# ArduinoShield.net
KiCad netlist of a schematic drawn in EAGLE
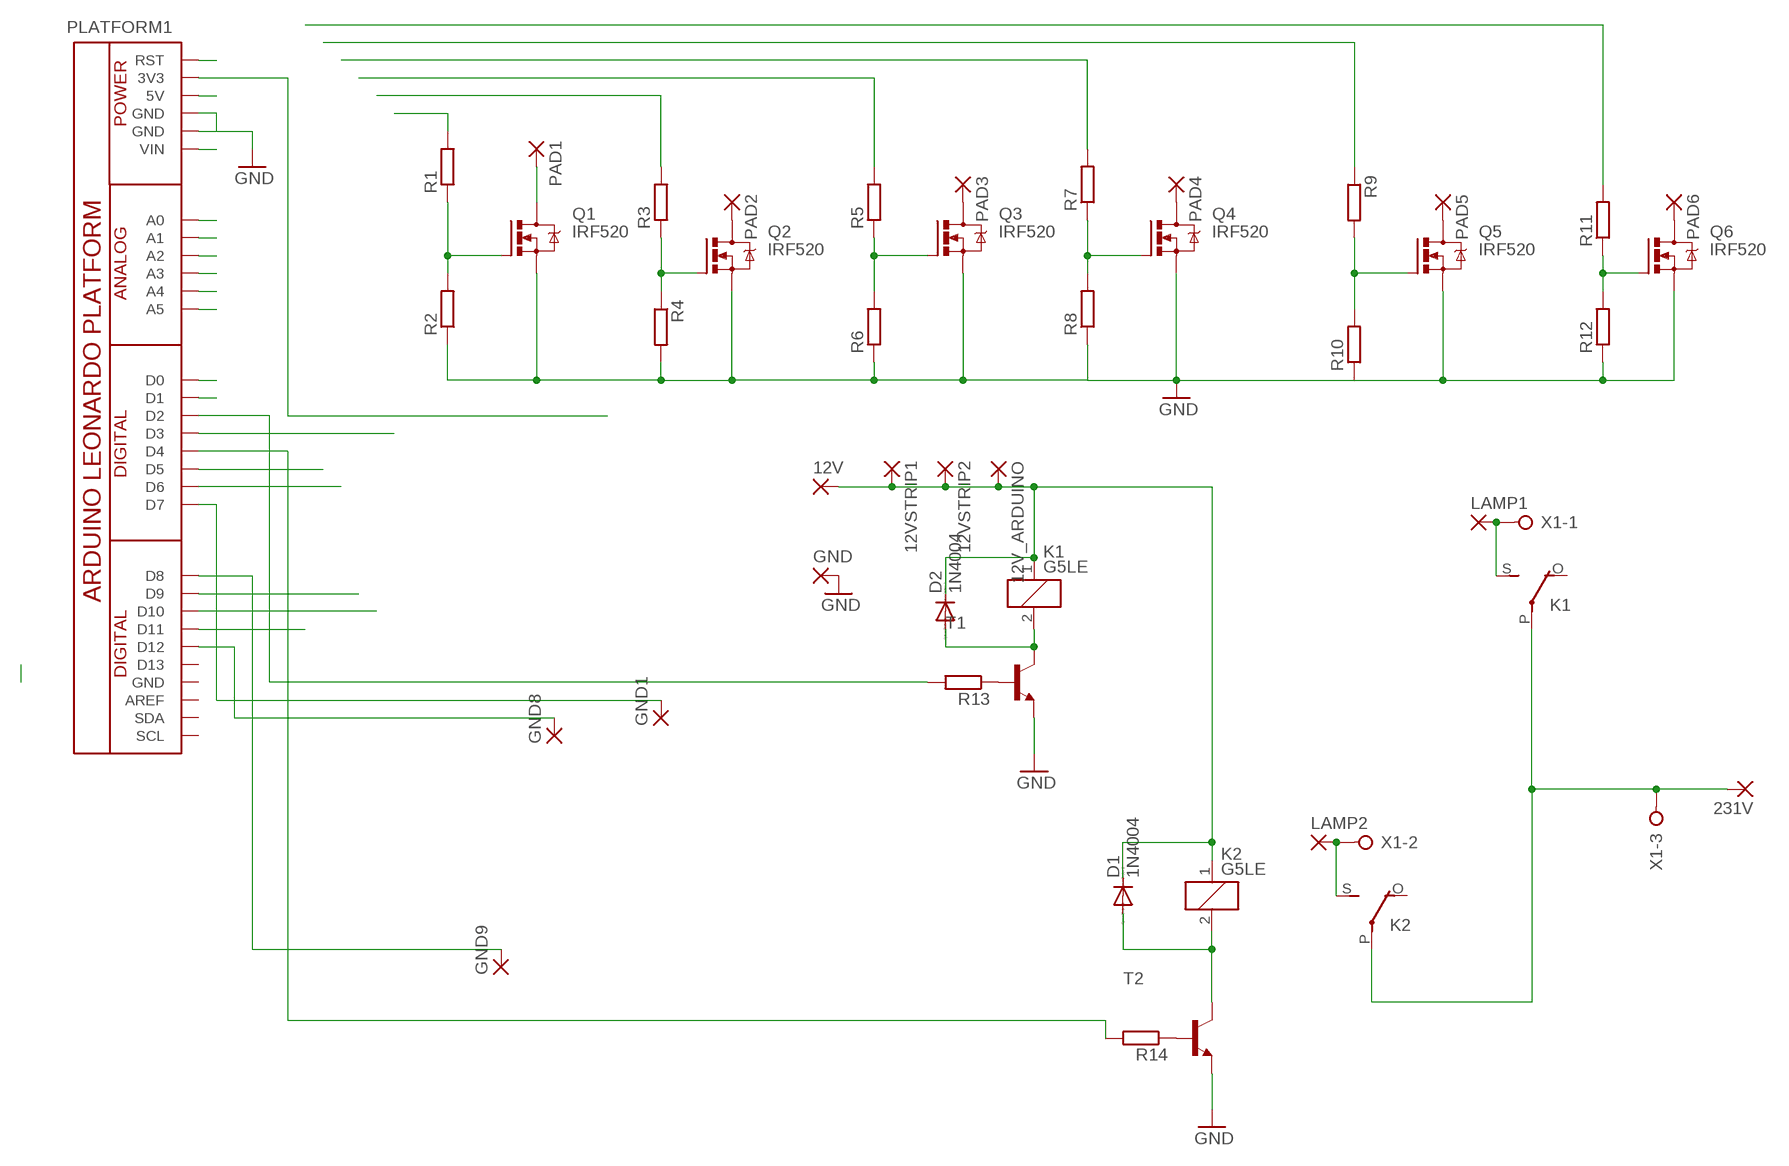
[diagram p0: schematic, sheet 1]

(export (version "E")
  (design (tool "Eeschema 10.0.6"))
  (components
    (comp (ref "12V")
      (value "WIREPAD1,6/0,8")
      (footprint "eagle-import:1,6_0,8")
      (libsource (lib "eagle-import") (part "WIREPAD1,6/0,8"))
    )
    (comp (ref "12VSTRIP1")
      (value "WIREPAD1,6/0,8")
      (footprint "eagle-import:1,6_0,8")
      (libsource (lib "eagle-import") (part "WIREPAD1,6/0,8"))
    )
    (comp (ref "12VSTRIP2")
      (value "WIREPAD1,6/0,8")
      (footprint "eagle-import:1,6_0,8")
      (libsource (lib "eagle-import") (part "WIREPAD1,6/0,8"))
    )
    (comp (ref "12V_ARDUINO")
      (value "WIREPAD1,6/0,8")
      (footprint "eagle-import:1,6_0,8")
      (libsource (lib "eagle-import") (part "WIREPAD1,6/0,8"))
    )
    (comp (ref "231V")
      (value "WIREPAD1,6/0,8")
      (footprint "eagle-import:1,6_0,8")
      (libsource (lib "eagle-import") (part "WIREPAD1,6/0,8"))
    )
    (comp (ref "D1")
      (value "1N4004")
      (footprint "eagle-import:DO41-10")
      (libsource (lib "eagle-import") (part "1N4004"))
    )
    (comp (ref "D2")
      (value "1N4004")
      (footprint "eagle-import:DO41-10")
      (libsource (lib "eagle-import") (part "1N4004"))
    )
    (comp (ref "GND")
      (value "WIREPAD1,6/0,8")
      (footprint "eagle-import:1,6_0,8")
      (libsource (lib "eagle-import") (part "WIREPAD1,6/0,8"))
    )
    (comp (ref "GND1")
      (value "WIREPAD1,6/0,8")
      (footprint "eagle-import:1,6_0,8")
      (libsource (lib "eagle-import") (part "WIREPAD1,6/0,8"))
    )
    (comp (ref "GND8")
      (value "WIREPAD1,6/0,8")
      (footprint "eagle-import:1,6_0,8")
      (libsource (lib "eagle-import") (part "WIREPAD1,6/0,8"))
    )
    (comp (ref "GND9")
      (value "WIREPAD1,6/0,8")
      (footprint "eagle-import:1,6_0,8")
      (libsource (lib "eagle-import") (part "WIREPAD1,6/0,8"))
    )
    (comp (ref "K1")
      (value "G5LE")
      (footprint "eagle-import:G5LE")
      (libsource (lib "eagle-import") (part "G5LE"))
    )
    (comp (ref "K2")
      (value "G5LE")
      (footprint "eagle-import:G5LE")
      (libsource (lib "eagle-import") (part "G5LE"))
    )
    (comp (ref "LAMP1")
      (value "WIREPAD1,6/0,8")
      (footprint "eagle-import:1,6_0,8")
      (libsource (lib "eagle-import") (part "WIREPAD1,6/0,8"))
    )
    (comp (ref "LAMP2")
      (value "WIREPAD1,6/0,8")
      (footprint "eagle-import:1,6_0,8")
      (libsource (lib "eagle-import") (part "WIREPAD1,6/0,8"))
    )
    (comp (ref "PAD1")
      (value "WIREPAD1,6/0,8")
      (footprint "eagle-import:1,6_0,8")
      (libsource (lib "eagle-import") (part "WIREPAD1,6/0,8"))
    )
    (comp (ref "PAD2")
      (value "WIREPAD1,6/0,8")
      (footprint "eagle-import:1,6_0,8")
      (libsource (lib "eagle-import") (part "WIREPAD1,6/0,8"))
    )
    (comp (ref "PAD3")
      (value "WIREPAD1,6/0,8")
      (footprint "eagle-import:1,6_0,8")
      (libsource (lib "eagle-import") (part "WIREPAD1,6/0,8"))
    )
    (comp (ref "PAD4")
      (value "WIREPAD1,6/0,8")
      (footprint "eagle-import:1,6_0,8")
      (libsource (lib "eagle-import") (part "WIREPAD1,6/0,8"))
    )
    (comp (ref "PAD5")
      (value "WIREPAD1,6/0,8")
      (footprint "eagle-import:1,6_0,8")
      (libsource (lib "eagle-import") (part "WIREPAD1,6/0,8"))
    )
    (comp (ref "PAD6")
      (value "WIREPAD1,6/0,8")
      (footprint "eagle-import:1,6_0,8")
      (libsource (lib "eagle-import") (part "WIREPAD1,6/0,8"))
    )
    (comp (ref "PLATFORM1")
      (value "1xPN1x10+1xPN1x8+2xPN1x6")
      (footprint "eagle-import:ARDUINO-LEONARDO-PLATFORM")
      (libsource (lib "eagle-import") (part "ARDUINO_LEONARDO"))
    )
    (comp (ref "Q1")
      (value "IRF520")
      (footprint "eagle-import:TO220BV")
      (libsource (lib "eagle-import") (part "IRF520"))
    )
    (comp (ref "Q2")
      (value "IRF520")
      (footprint "eagle-import:TO220BV")
      (libsource (lib "eagle-import") (part "IRF520"))
    )
    (comp (ref "Q3")
      (value "IRF520")
      (footprint "eagle-import:TO220BV")
      (libsource (lib "eagle-import") (part "IRF520"))
    )
    (comp (ref "Q4")
      (value "IRF520")
      (footprint "eagle-import:TO220BV")
      (libsource (lib "eagle-import") (part "IRF520"))
    )
    (comp (ref "Q5")
      (value "IRF520")
      (footprint "eagle-import:TO220BV")
      (libsource (lib "eagle-import") (part "IRF520"))
    )
    (comp (ref "Q6")
      (value "IRF520")
      (footprint "eagle-import:TO220BV")
      (libsource (lib "eagle-import") (part "IRF520"))
    )
    (comp (ref "R1")
      (value "R-EU_0207/7")
      (footprint "eagle-import:0207_7")
      (libsource (lib "eagle-import") (part "R-EU_0207/7"))
    )
    (comp (ref "R2")
      (value "R-EU_0207/7")
      (footprint "eagle-import:0207_7")
      (libsource (lib "eagle-import") (part "R-EU_0207/7"))
    )
    (comp (ref "R3")
      (value "R-EU_0207/7")
      (footprint "eagle-import:0207_7")
      (libsource (lib "eagle-import") (part "R-EU_0207/7"))
    )
    (comp (ref "R4")
      (value "R-EU_0207/7")
      (footprint "eagle-import:0207_7")
      (libsource (lib "eagle-import") (part "R-EU_0207/7"))
    )
    (comp (ref "R5")
      (value "R-EU_0207/7")
      (footprint "eagle-import:0207_7")
      (libsource (lib "eagle-import") (part "R-EU_0207/7"))
    )
    (comp (ref "R6")
      (value "R-EU_0207/7")
      (footprint "eagle-import:0207_7")
      (libsource (lib "eagle-import") (part "R-EU_0207/7"))
    )
    (comp (ref "R7")
      (value "R-EU_0207/7")
      (footprint "eagle-import:0207_7")
      (libsource (lib "eagle-import") (part "R-EU_0207/7"))
    )
    (comp (ref "R8")
      (value "R-EU_0207/7")
      (footprint "eagle-import:0207_7")
      (libsource (lib "eagle-import") (part "R-EU_0207/7"))
    )
    (comp (ref "R9")
      (value "R-EU_0207/7")
      (footprint "eagle-import:0207_7")
      (libsource (lib "eagle-import") (part "R-EU_0207/7"))
    )
    (comp (ref "R10")
      (value "R-EU_0207/7")
      (footprint "eagle-import:0207_7")
      (libsource (lib "eagle-import") (part "R-EU_0207/7"))
    )
    (comp (ref "R11")
      (value "R-EU_0207/7")
      (footprint "eagle-import:0207_7")
      (libsource (lib "eagle-import") (part "R-EU_0207/7"))
    )
    (comp (ref "R12")
      (value "R-EU_0207/7")
      (footprint "eagle-import:0207_7")
      (libsource (lib "eagle-import") (part "R-EU_0207/7"))
    )
    (comp (ref "R13")
      (value "R-EU_0207/7")
      (footprint "eagle-import:0207_7")
      (libsource (lib "eagle-import") (part "R-EU_0207/7"))
    )
    (comp (ref "R14")
      (value "R-EU_0207/7")
      (footprint "eagle-import:0207_7")
      (libsource (lib "eagle-import") (part "R-EU_0207/7"))
    )
    (comp (ref "T1")
      (value "BC547-NPN-TO92-CBE")
      (footprint "eagle-import:TO92-CBE")
      (libsource (lib "eagle-import") (part "-NPN-TO92-CBEBC547"))
    )
    (comp (ref "T2")
      (value "BC547-NPN-TO92-CBE")
      (footprint "eagle-import:TO92-CBE")
      (libsource (lib "eagle-import") (part "-NPN-TO92-CBEBC547"))
    )
    (comp (ref "X1")
      (value "W237-3E")
      (footprint "eagle-import:W237-3E")
      (libsource (lib "eagle-import") (part "W237-3E"))
    )
  )
  (nets
    (net (code "1") (name "/N$14") (class "Default")
      (node (ref "PLATFORM1") (pin "D5") (pinfunction "D5_D5") (pintype "bidirectional"))
      (node (ref "R3") (pin "2") (pinfunction "2_2") (pintype "passive"))
    )
    (net (code "2") (name "/N$15") (class "Default")
      (node (ref "PLATFORM1") (pin "D6") (pinfunction "D6_D6") (pintype "bidirectional"))
      (node (ref "R5") (pin "2") (pinfunction "2_2") (pintype "passive"))
    )
    (net (code "3") (name "/N$45") (class "Default")
      (node (ref "PLATFORM1") (pin "D3") (pinfunction "D3_D3") (pintype "bidirectional"))
      (node (ref "R1") (pin "2") (pinfunction "2_2") (pintype "passive"))
    )
    (net (code "4") (name "GND") (class "Default")
      (node (ref "GND") (pin "1") (pinfunction "P_1") (pintype "passive"))
      (node (ref "PLATFORM1") (pin "GND") (pinfunction "GND_GND") (pintype "bidirectional"))
      (node (ref "PLATFORM1") (pin "GND@1") (pinfunction "GND_GND@1") (pintype "bidirectional"))
      (node (ref "Q1") (pin "S") (pinfunction "S_S") (pintype "passive"))
      (node (ref "Q2") (pin "S") (pinfunction "S_S") (pintype "passive"))
      (node (ref "Q3") (pin "S") (pinfunction "S_S") (pintype "passive"))
      (node (ref "Q4") (pin "S") (pinfunction "S_S") (pintype "passive"))
      (node (ref "Q5") (pin "S") (pinfunction "S_S") (pintype "passive"))
      (node (ref "Q6") (pin "S") (pinfunction "S_S") (pintype "passive"))
      (node (ref "R10") (pin "1") (pinfunction "1_1") (pintype "passive"))
      (node (ref "R12") (pin "1") (pinfunction "1_1") (pintype "passive"))
      (node (ref "R2") (pin "1") (pinfunction "1_1") (pintype "passive"))
      (node (ref "R4") (pin "2") (pinfunction "2_2") (pintype "passive"))
      (node (ref "R6") (pin "1") (pinfunction "1_1") (pintype "passive"))
      (node (ref "R8") (pin "1") (pinfunction "1_1") (pintype "passive"))
      (node (ref "T1") (pin "E") (pinfunction "E_E") (pintype "passive"))
      (node (ref "T2") (pin "E") (pinfunction "E_E") (pintype "passive"))
    )
    (net (code "5") (name "Net-(12V-P)") (class "Default")
      (node (ref "12V") (pin "1") (pinfunction "P_1") (pintype "passive"))
      (node (ref "12VSTRIP1") (pin "1") (pinfunction "P_1") (pintype "passive"))
      (node (ref "12VSTRIP2") (pin "1") (pinfunction "P_1") (pintype "passive"))
      (node (ref "12V_ARDUINO") (pin "1") (pinfunction "P_1") (pintype "passive"))
      (node (ref "D1") (pin "C") (pinfunction "C_C") (pintype "passive"))
      (node (ref "D2") (pin "C") (pinfunction "C_C") (pintype "passive"))
      (node (ref "K1") (pin "1") (pinfunction "1_1") (pintype "passive"))
      (node (ref "K2") (pin "1") (pinfunction "1_1") (pintype "passive"))
    )
    (net (code "6") (name "Net-(231V-P)") (class "Default")
      (node (ref "231V") (pin "1") (pinfunction "P_1") (pintype "passive"))
      (node (ref "K1") (pin "P") (pinfunction "P_P") (pintype "passive"))
      (node (ref "K2") (pin "P") (pinfunction "P_P") (pintype "passive"))
      (node (ref "X1") (pin "3") (pinfunction "KL_3") (pintype "passive"))
    )
    (net (code "7") (name "Net-(D1-PadA)") (class "Default")
      (node (ref "D1") (pin "A") (pinfunction "A_A") (pintype "passive"))
      (node (ref "K2") (pin "2") (pinfunction "2_2") (pintype "passive"))
      (node (ref "T2") (pin "C") (pinfunction "C_C") (pintype "passive"))
    )
    (net (code "8") (name "Net-(D2-PadA)") (class "Default")
      (node (ref "D2") (pin "A") (pinfunction "A_A") (pintype "passive"))
      (node (ref "K1") (pin "2") (pinfunction "2_2") (pintype "passive"))
      (node (ref "T1") (pin "C") (pinfunction "C_C") (pintype "passive"))
    )
    (net (code "9") (name "Net-(GND1-P)") (class "Default")
      (node (ref "GND1") (pin "1") (pinfunction "P_1") (pintype "passive"))
      (node (ref "PLATFORM1") (pin "D7") (pinfunction "D7_D7") (pintype "bidirectional"))
    )
    (net (code "10") (name "Net-(GND8-P)") (class "Default")
      (node (ref "GND8") (pin "1") (pinfunction "P_1") (pintype "passive"))
      (node (ref "PLATFORM1") (pin "D12") (pinfunction "D12_D12") (pintype "bidirectional"))
    )
    (net (code "11") (name "Net-(GND9-P)") (class "Default")
      (node (ref "GND9") (pin "1") (pinfunction "P_1") (pintype "passive"))
      (node (ref "PLATFORM1") (pin "D8") (pinfunction "D8_D8") (pintype "bidirectional"))
    )
    (net (code "12") (name "Net-(LAMP1-P)") (class "Default")
      (node (ref "K1") (pin "S") (pinfunction "S_S") (pintype "passive"))
      (node (ref "LAMP1") (pin "1") (pinfunction "P_1") (pintype "passive"))
      (node (ref "X1") (pin "1") (pinfunction "KL_1") (pintype "passive"))
    )
    (net (code "13") (name "Net-(LAMP2-P)") (class "Default")
      (node (ref "K2") (pin "S") (pinfunction "S_S") (pintype "passive"))
      (node (ref "LAMP2") (pin "1") (pinfunction "P_1") (pintype "passive"))
      (node (ref "X1") (pin "2") (pinfunction "KL_2") (pintype "passive"))
    )
    (net (code "14") (name "Net-(PAD1-P)") (class "Default")
      (node (ref "PAD1") (pin "1") (pinfunction "P_1") (pintype "passive"))
      (node (ref "Q1") (pin "D") (pinfunction "D_D") (pintype "passive"))
    )
    (net (code "15") (name "Net-(PAD2-P)") (class "Default")
      (node (ref "PAD2") (pin "1") (pinfunction "P_1") (pintype "passive"))
      (node (ref "Q2") (pin "D") (pinfunction "D_D") (pintype "passive"))
    )
    (net (code "16") (name "Net-(PAD3-P)") (class "Default")
      (node (ref "PAD3") (pin "1") (pinfunction "P_1") (pintype "passive"))
      (node (ref "Q3") (pin "D") (pinfunction "D_D") (pintype "passive"))
    )
    (net (code "17") (name "Net-(PAD4-P)") (class "Default")
      (node (ref "PAD4") (pin "1") (pinfunction "P_1") (pintype "passive"))
      (node (ref "Q4") (pin "D") (pinfunction "D_D") (pintype "passive"))
    )
    (net (code "18") (name "Net-(PAD5-P)") (class "Default")
      (node (ref "PAD5") (pin "1") (pinfunction "P_1") (pintype "passive"))
      (node (ref "Q5") (pin "D") (pinfunction "D_D") (pintype "passive"))
    )
    (net (code "19") (name "Net-(PAD6-P)") (class "Default")
      (node (ref "PAD6") (pin "1") (pinfunction "P_1") (pintype "passive"))
      (node (ref "Q6") (pin "D") (pinfunction "D_D") (pintype "passive"))
    )
    (net (code "20") (name "Net-(PLATFORM1-PadD2)") (class "Default")
      (node (ref "PLATFORM1") (pin "D2") (pinfunction "D2_D2") (pintype "bidirectional"))
      (node (ref "R13") (pin "2") (pinfunction "2_2") (pintype "passive"))
    )
    (net (code "21") (name "Net-(PLATFORM1-PadD4)") (class "Default")
      (node (ref "PLATFORM1") (pin "D4") (pinfunction "D4_D4") (pintype "bidirectional"))
      (node (ref "R14") (pin "2") (pinfunction "2_2") (pintype "passive"))
    )
    (net (code "22") (name "Net-(Q1-PadG)") (class "Default")
      (node (ref "Q1") (pin "G") (pinfunction "G_G") (pintype "passive"))
      (node (ref "R1") (pin "1") (pinfunction "1_1") (pintype "passive"))
      (node (ref "R2") (pin "2") (pinfunction "2_2") (pintype "passive"))
    )
    (net (code "23") (name "Net-(Q2-PadG)") (class "Default")
      (node (ref "Q2") (pin "G") (pinfunction "G_G") (pintype "passive"))
      (node (ref "R3") (pin "1") (pinfunction "1_1") (pintype "passive"))
      (node (ref "R4") (pin "1") (pinfunction "1_1") (pintype "passive"))
    )
    (net (code "24") (name "Net-(Q3-PadG)") (class "Default")
      (node (ref "Q3") (pin "G") (pinfunction "G_G") (pintype "passive"))
      (node (ref "R5") (pin "1") (pinfunction "1_1") (pintype "passive"))
      (node (ref "R6") (pin "2") (pinfunction "2_2") (pintype "passive"))
    )
    (net (code "25") (name "Net-(Q4-PadG)") (class "Default")
      (node (ref "Q4") (pin "G") (pinfunction "G_G") (pintype "passive"))
      (node (ref "R7") (pin "1") (pinfunction "1_1") (pintype "passive"))
      (node (ref "R8") (pin "2") (pinfunction "2_2") (pintype "passive"))
    )
    (net (code "26") (name "Net-(Q5-PadG)") (class "Default")
      (node (ref "Q5") (pin "G") (pinfunction "G_G") (pintype "passive"))
      (node (ref "R10") (pin "2") (pinfunction "2_2") (pintype "passive"))
      (node (ref "R9") (pin "2") (pinfunction "2_2") (pintype "passive"))
    )
    (net (code "27") (name "Net-(Q6-PadG)") (class "Default")
      (node (ref "Q6") (pin "G") (pinfunction "G_G") (pintype "passive"))
      (node (ref "R11") (pin "1") (pinfunction "1_1") (pintype "passive"))
      (node (ref "R12") (pin "2") (pinfunction "2_2") (pintype "passive"))
    )
    (net (code "28") (name "Net-(R13-Pad1)") (class "Default")
      (node (ref "R13") (pin "1") (pinfunction "1_1") (pintype "passive"))
      (node (ref "T1") (pin "B") (pinfunction "B_B") (pintype "passive"))
    )
    (net (code "29") (name "Net-(R14-Pad1)") (class "Default")
      (node (ref "R14") (pin "1") (pinfunction "1_1") (pintype "passive"))
      (node (ref "T2") (pin "B") (pinfunction "B_B") (pintype "passive"))
    )
    (net (code "30") (name "unconnected-(K1-PadO)") (class "Default")
      (node (ref "K1") (pin "O") (pinfunction "O_O") (pintype "passive"))
    )
    (net (code "31") (name "unconnected-(K2-PadO)") (class "Default")
      (node (ref "K2") (pin "O") (pinfunction "O_O") (pintype "passive"))
    )
    (net (code "32") (name "unconnected-(PLATFORM1-GND-PadGND@2)") (class "Default")
      (node (ref "PLATFORM1") (pin "GND@2") (pinfunction "GND_GND@2") (pintype "bidirectional"))
    )
    (net (code "33") (name "unconnected-(PLATFORM1-Pad3V3)") (class "Default")
      (node (ref "PLATFORM1") (pin "3V3") (pinfunction "3V3_3V3") (pintype "bidirectional"))
    )
    (net (code "34") (name "unconnected-(PLATFORM1-Pad5V)") (class "Default")
      (node (ref "PLATFORM1") (pin "5V") (pinfunction "5V_5V") (pintype "bidirectional"))
    )
    (net (code "35") (name "unconnected-(PLATFORM1-PadA0)") (class "Default")
      (node (ref "PLATFORM1") (pin "A0") (pinfunction "A0_A0") (pintype "bidirectional"))
    )
    (net (code "36") (name "unconnected-(PLATFORM1-PadA1)") (class "Default")
      (node (ref "PLATFORM1") (pin "A1") (pinfunction "A1_A1") (pintype "bidirectional"))
    )
    (net (code "37") (name "unconnected-(PLATFORM1-PadA2)") (class "Default")
      (node (ref "PLATFORM1") (pin "A2") (pinfunction "A2_A2") (pintype "bidirectional"))
    )
    (net (code "38") (name "unconnected-(PLATFORM1-PadA3)") (class "Default")
      (node (ref "PLATFORM1") (pin "A3") (pinfunction "A3_A3") (pintype "bidirectional"))
    )
    (net (code "39") (name "unconnected-(PLATFORM1-PadA4)") (class "Default")
      (node (ref "PLATFORM1") (pin "A4") (pinfunction "A4_A4") (pintype "bidirectional"))
    )
    (net (code "40") (name "unconnected-(PLATFORM1-PadA5)") (class "Default")
      (node (ref "PLATFORM1") (pin "A5") (pinfunction "A5_A5") (pintype "bidirectional"))
    )
    (net (code "41") (name "unconnected-(PLATFORM1-PadAREF)") (class "Default")
      (node (ref "PLATFORM1") (pin "AREF") (pinfunction "AREF_AREF") (pintype "bidirectional"))
    )
    (net (code "42") (name "unconnected-(PLATFORM1-PadD0)") (class "Default")
      (node (ref "PLATFORM1") (pin "D0") (pinfunction "D0_D0") (pintype "bidirectional"))
    )
    (net (code "43") (name "unconnected-(PLATFORM1-PadD1)") (class "Default")
      (node (ref "PLATFORM1") (pin "D1") (pinfunction "D1_D1") (pintype "bidirectional"))
    )
    (net (code "44") (name "unconnected-(PLATFORM1-PadD9)") (class "Default")
      (node (ref "PLATFORM1") (pin "D9") (pinfunction "D9_D9") (pintype "bidirectional"))
    )
    (net (code "45") (name "unconnected-(PLATFORM1-PadD10)") (class "Default")
      (node (ref "PLATFORM1") (pin "D10") (pinfunction "D10_D10") (pintype "bidirectional"))
    )
    (net (code "46") (name "unconnected-(PLATFORM1-PadD11)") (class "Default")
      (node (ref "PLATFORM1") (pin "D11") (pinfunction "D11_D11") (pintype "bidirectional"))
    )
    (net (code "47") (name "unconnected-(PLATFORM1-PadD13)") (class "Default")
      (node (ref "PLATFORM1") (pin "D13") (pinfunction "D13_D13") (pintype "bidirectional"))
    )
    (net (code "48") (name "unconnected-(PLATFORM1-PadRST)") (class "Default")
      (node (ref "PLATFORM1") (pin "RST") (pinfunction "RST_RST") (pintype "bidirectional"))
    )
    (net (code "49") (name "unconnected-(PLATFORM1-PadSCL)") (class "Default")
      (node (ref "PLATFORM1") (pin "SCL") (pinfunction "SCL_SCL") (pintype "bidirectional"))
    )
    (net (code "50") (name "unconnected-(PLATFORM1-PadSDA)") (class "Default")
      (node (ref "PLATFORM1") (pin "SDA") (pinfunction "SDA_SDA") (pintype "bidirectional"))
    )
    (net (code "51") (name "unconnected-(PLATFORM1-PadVIN)") (class "Default")
      (node (ref "PLATFORM1") (pin "VIN") (pinfunction "VIN_VIN") (pintype "bidirectional"))
    )
    (net (code "52") (name "unconnected-(R7-Pad2)") (class "Default")
      (node (ref "R7") (pin "2") (pinfunction "2_2") (pintype "passive"))
    )
    (net (code "53") (name "unconnected-(R9-Pad1)") (class "Default")
      (node (ref "R9") (pin "1") (pinfunction "1_1") (pintype "passive"))
    )
    (net (code "54") (name "unconnected-(R11-Pad2)") (class "Default")
      (node (ref "R11") (pin "2") (pinfunction "2_2") (pintype "passive"))
    )
  )
)
